# LED_SEMISEGMENT.net
KiCad netlist of a schematic drawn in Altium Designer
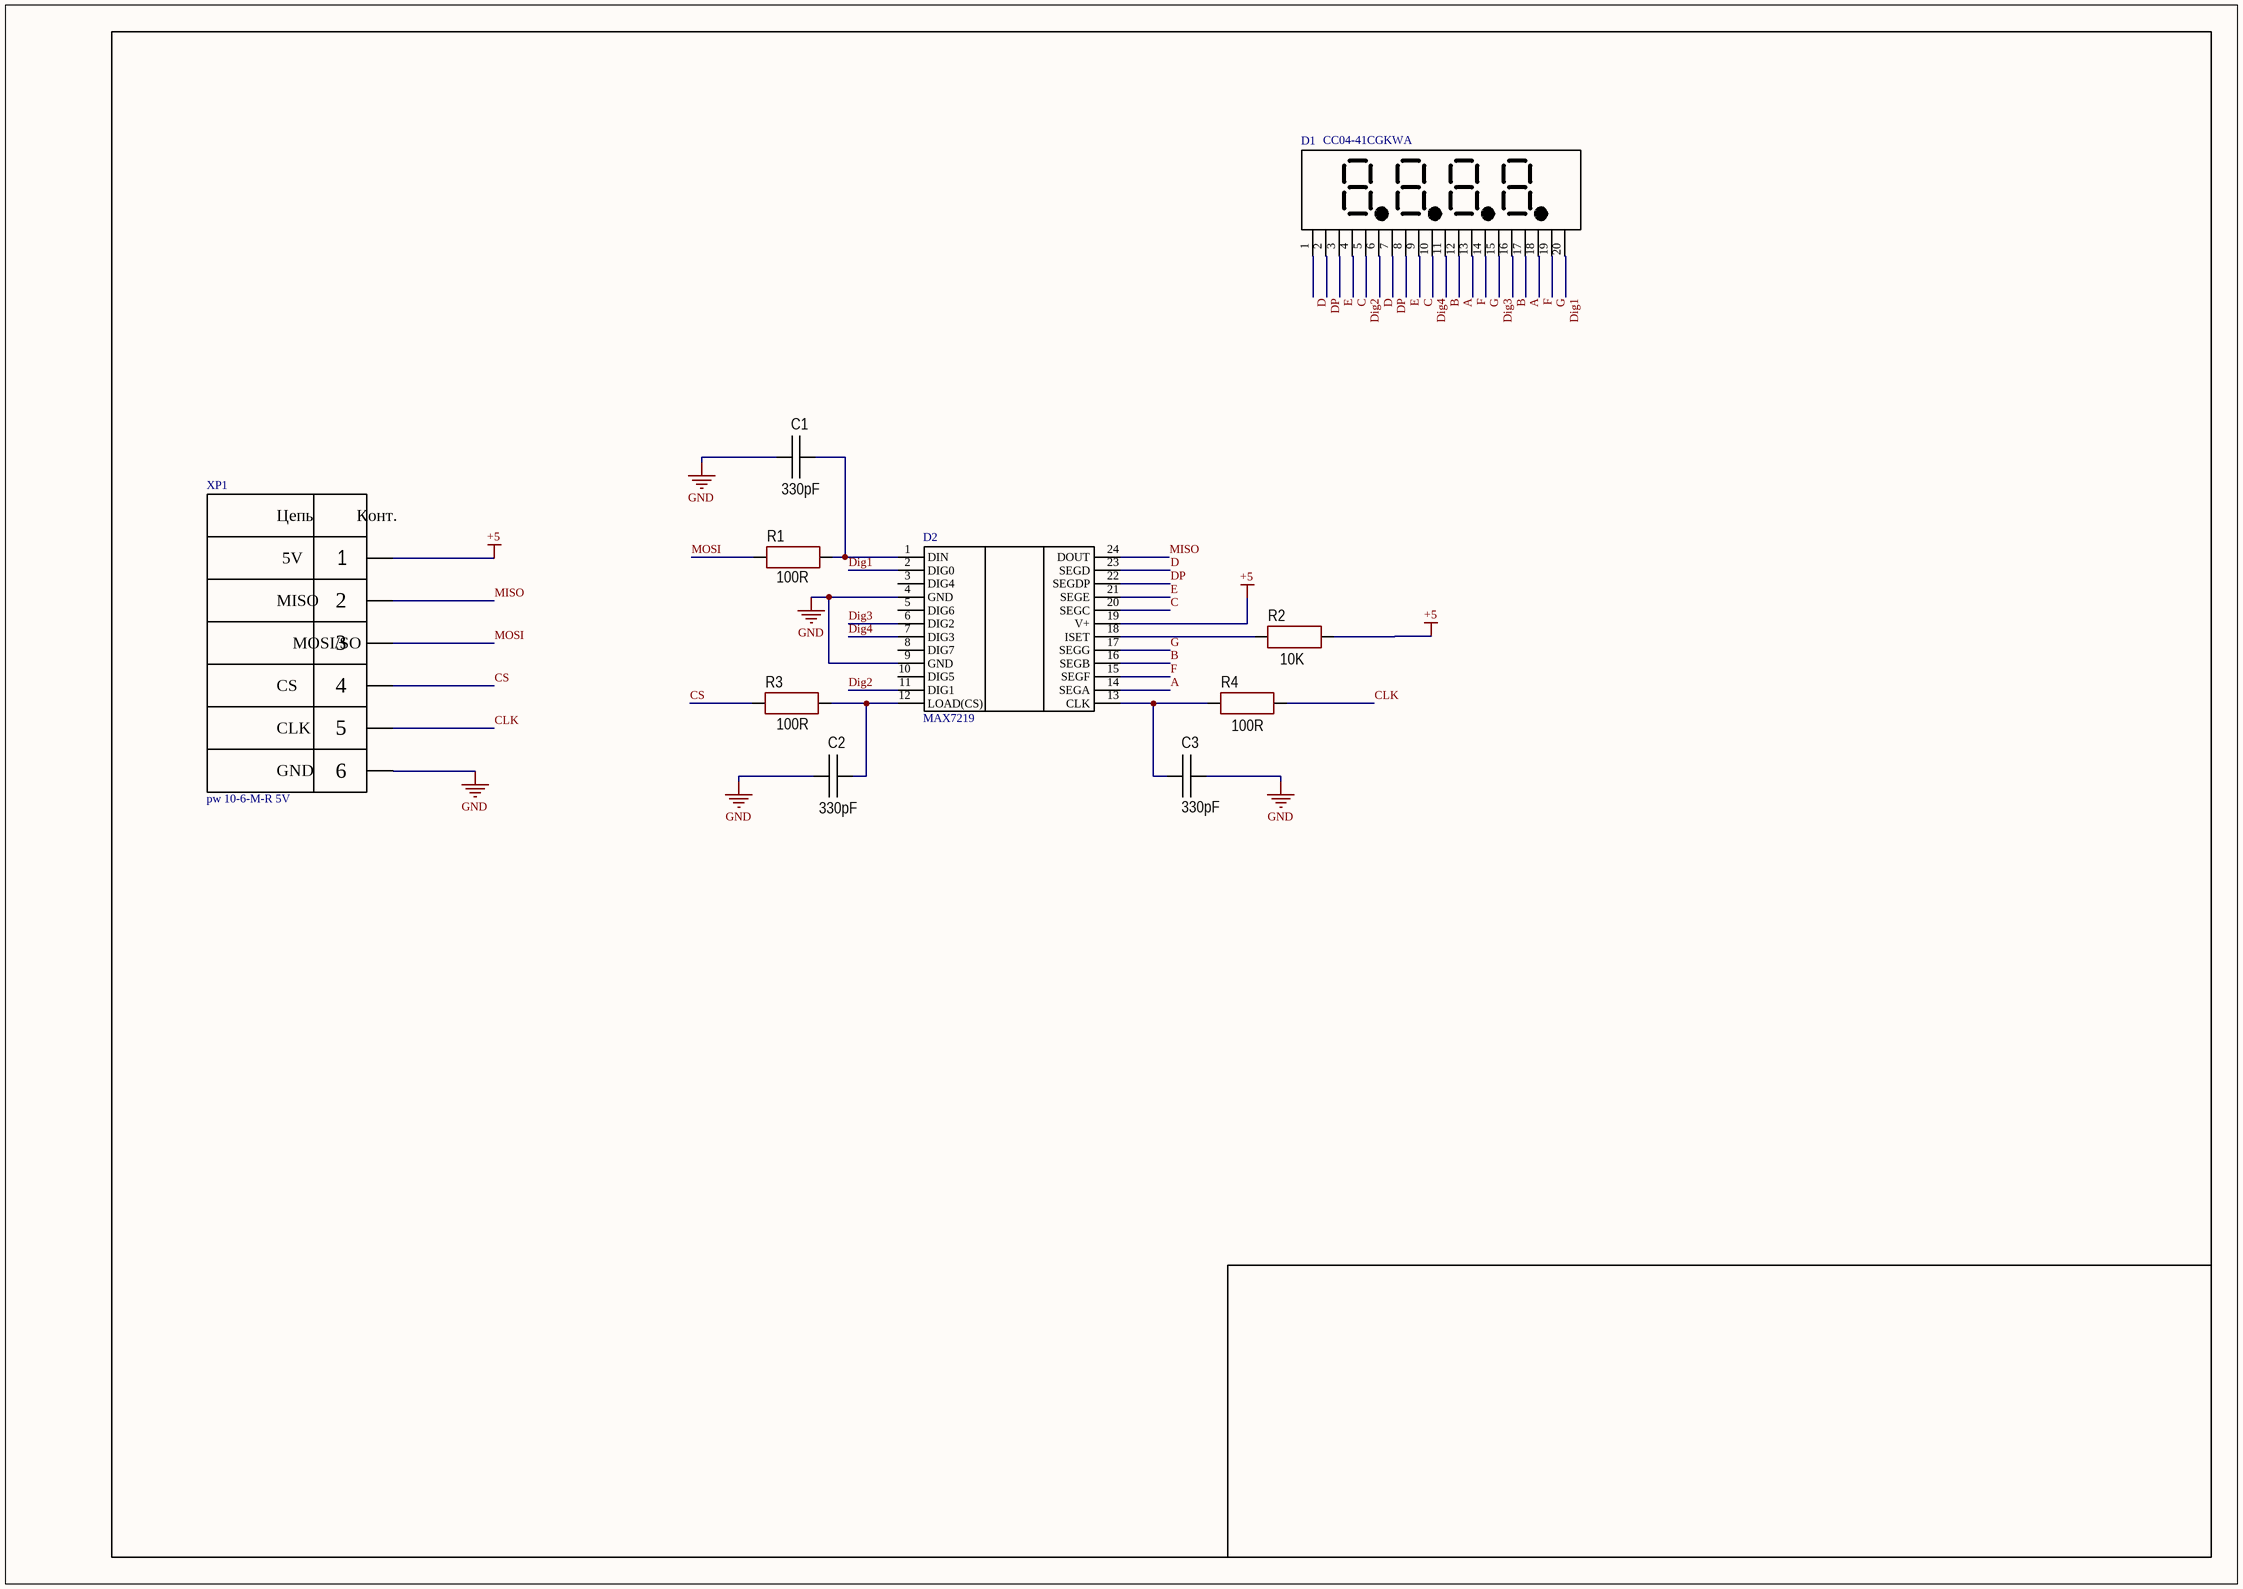
[diagram p0: LED_SEMISEGMENT.SchDoc]

(export (version "E")
  (design (tool "Eeschema 10.0.6"))
  (components
    (comp (ref "C1")
      (value "330pF")
      (footprint "CAP: 0805")
      (fields (field (name "VALUEMANUFACTURERPARTNUMBER") "Ceramic capacitor, 330pF, X7R, , , 0805, "))
      (libsource (lib "Capacitor") (part "Ceramic_0805"))
    )
    (comp (ref "C2")
      (value "330pF")
      (footprint "CAP: 0805")
      (fields (field (name "VALUEMANUFACTURERPARTNUMBER") "Ceramic capacitor, 330pF, X7R, , , 0805, "))
      (libsource (lib "Capacitor") (part "Ceramic_0805"))
    )
    (comp (ref "C3")
      (value "330pF")
      (footprint "CAP: 0805")
      (fields (field (name "VALUEMANUFACTURERPARTNUMBER") "Ceramic capacitor, 330pF, X7R, , , 0805, "))
      (libsource (lib "Capacitor") (part "Ceramic_0805"))
    )
    (comp (ref "D1")
      (value "CC04-41CGKWA")
      (footprint "7 segment x4")
      (libsource (lib "Integrated_Library") (part "LED_7x4"))
    )
    (comp (ref "D2")
      (value "MAX7219")
      (footprint "SOIC127P1030X265-24N")
      (libsource (lib "Integrated_Library") (part "MAX7219"))
    )
    (comp (ref "R1")
      (value "100R")
      (footprint "RES: 0805")
      (fields (field (name "VALUEMANUFACTURERPARTNUMBER") ", 100R, , 0805, , "))
      (libsource (lib "Resistor") (part "Resistor_0805"))
    )
    (comp (ref "R2")
      (value "10K")
      (footprint "RES: 0805")
      (fields (field (name "VALUEMANUFACTURERPARTNUMBER") ", 10K, , 0805, , "))
      (libsource (lib "Resistor") (part "Resistor_0805"))
    )
    (comp (ref "R3")
      (value "100R")
      (footprint "RES: 0805")
      (libsource (lib "Resistor") (part "Resistor_0805"))
    )
    (comp (ref "R4")
      (value "100R")
      (footprint "RES: 0805")
      (fields (field (name "VALUEMANUFACTURERPARTNUMBER") ", 100R, , 0805, , "))
      (libsource (lib "Resistor") (part "Resistor_0805"))
    )
    (comp (ref "XP1")
      (value "pw 10-6-M-R 5V")
      (footprint "PW 10-6-M")
      (libsource (lib "Integrated_Library") (part "pw 10-6-M-R 5V"))
    )
  )
  (nets
    (net (code "1") (name "+5") (class "Default")
      (node (ref "D2") (pin "19") (pinfunction "V+_19") (pintype "passive"))
      (node (ref "R2") (pin "2") (pinfunction "2_2") (pintype "passive"))
      (node (ref "XP1") (pin "1") (pinfunction "1_1") (pintype "passive"))
    )
    (net (code "3") (name "/A") (class "Default")
      (node (ref "D1") (pin "12") (pinfunction "12_12") (pintype "passive"))
      (node (ref "D1") (pin "17") (pinfunction "17_17") (pintype "passive"))
      (node (ref "D2") (pin "14") (pinfunction "SEGA_14") (pintype "passive"))
    )
    (net (code "4") (name "/B") (class "Default")
      (node (ref "D1") (pin "11") (pinfunction "11_11") (pintype "passive"))
      (node (ref "D1") (pin "16") (pinfunction "16_16") (pintype "passive"))
      (node (ref "D2") (pin "16") (pinfunction "SEGB_16") (pintype "passive"))
    )
    (net (code "5") (name "/C") (class "Default")
      (node (ref "D1") (pin "4") (pinfunction "4_4") (pintype "passive"))
      (node (ref "D1") (pin "9") (pinfunction "9_9") (pintype "passive"))
      (node (ref "D2") (pin "20") (pinfunction "SEGC_20") (pintype "passive"))
    )
    (net (code "6") (name "/CLK") (class "Default")
      (node (ref "R4") (pin "2") (pinfunction "2_2") (pintype "passive"))
      (node (ref "XP1") (pin "5") (pinfunction "5_5") (pintype "passive"))
    )
    (net (code "7") (name "/CS") (class "Default")
      (node (ref "R3") (pin "1") (pinfunction "1_1") (pintype "passive"))
      (node (ref "XP1") (pin "4") (pinfunction "4_4") (pintype "passive"))
    )
    (net (code "8") (name "/D") (class "Default")
      (node (ref "D1") (pin "1") (pinfunction "1_1") (pintype "passive"))
      (node (ref "D1") (pin "6") (pinfunction "6_6") (pintype "passive"))
      (node (ref "D2") (pin "23") (pinfunction "SEGD_23") (pintype "passive"))
    )
    (net (code "9") (name "/DP") (class "Default")
      (node (ref "D1") (pin "2") (pinfunction "2_2") (pintype "passive"))
      (node (ref "D1") (pin "7") (pinfunction "7_7") (pintype "passive"))
      (node (ref "D2") (pin "22") (pinfunction "SEGDP_22") (pintype "passive"))
    )
    (net (code "10") (name "/Dig1") (class "Default")
      (node (ref "D1") (pin "20") (pinfunction "20_20") (pintype "passive"))
      (node (ref "D2") (pin "2") (pinfunction "DIG0_2") (pintype "passive"))
    )
    (net (code "11") (name "/Dig2") (class "Default")
      (node (ref "D1") (pin "5") (pinfunction "5_5") (pintype "passive"))
      (node (ref "D2") (pin "11") (pinfunction "DIG1_11") (pintype "passive"))
    )
    (net (code "12") (name "/Dig3") (class "Default")
      (node (ref "D1") (pin "15") (pinfunction "15_15") (pintype "passive"))
      (node (ref "D2") (pin "6") (pinfunction "DIG2_6") (pintype "passive"))
    )
    (net (code "13") (name "/Dig4") (class "Default")
      (node (ref "D1") (pin "10") (pinfunction "10_10") (pintype "passive"))
      (node (ref "D2") (pin "7") (pinfunction "DIG3_7") (pintype "passive"))
    )
    (net (code "14") (name "/E") (class "Default")
      (node (ref "D1") (pin "3") (pinfunction "3_3") (pintype "passive"))
      (node (ref "D1") (pin "8") (pinfunction "8_8") (pintype "passive"))
      (node (ref "D2") (pin "21") (pinfunction "SEGE_21") (pintype "passive"))
    )
    (net (code "15") (name "/F") (class "Default")
      (node (ref "D1") (pin "13") (pinfunction "13_13") (pintype "passive"))
      (node (ref "D1") (pin "18") (pinfunction "18_18") (pintype "passive"))
      (node (ref "D2") (pin "15") (pinfunction "SEGF_15") (pintype "passive"))
    )
    (net (code "16") (name "/G") (class "Default")
      (node (ref "D1") (pin "14") (pinfunction "14_14") (pintype "passive"))
      (node (ref "D1") (pin "19") (pinfunction "19_19") (pintype "passive"))
      (node (ref "D2") (pin "17") (pinfunction "SEGG_17") (pintype "passive"))
    )
    (net (code "17") (name "/MISO") (class "Default")
      (node (ref "D2") (pin "24") (pinfunction "DOUT_24") (pintype "passive"))
      (node (ref "XP1") (pin "2") (pinfunction "2_2") (pintype "passive"))
    )
    (net (code "18") (name "/MOSI") (class "Default")
      (node (ref "R1") (pin "1") (pinfunction "1_1") (pintype "passive"))
      (node (ref "XP1") (pin "3") (pinfunction "3_3") (pintype "passive"))
    )
    (net (code "19") (name "GND") (class "Default")
      (node (ref "C1") (pin "2") (pinfunction "2_2") (pintype "power_in"))
      (node (ref "C2") (pin "2") (pinfunction "2_2") (pintype "power_in"))
      (node (ref "C3") (pin "2") (pinfunction "2_2") (pintype "power_in"))
      (node (ref "D2") (pin "4") (pinfunction "GND_4") (pintype "passive"))
      (node (ref "D2") (pin "9") (pinfunction "GND_9") (pintype "passive"))
      (node (ref "XP1") (pin "6") (pinfunction "6_6") (pintype "passive"))
    )
    (net (code "20") (name "Net-(D2-CLK)") (class "Default")
      (node (ref "C3") (pin "1") (pinfunction "1_1") (pintype "power_in"))
      (node (ref "D2") (pin "13") (pinfunction "CLK_13") (pintype "passive"))
      (node (ref "R4") (pin "1") (pinfunction "1_1") (pintype "passive"))
    )
    (net (code "21") (name "Net-(D2-DIN)") (class "Default")
      (node (ref "C1") (pin "1") (pinfunction "1_1") (pintype "power_in"))
      (node (ref "D2") (pin "1") (pinfunction "DIN_1") (pintype "passive"))
      (node (ref "R1") (pin "2") (pinfunction "2_2") (pintype "passive"))
    )
    (net (code "22") (name "Net-(D2-ISET)") (class "Default")
      (node (ref "D2") (pin "18") (pinfunction "ISET_18") (pintype "passive"))
      (node (ref "R2") (pin "1") (pinfunction "1_1") (pintype "passive"))
    )
    (net (code "23") (name "Net-(D2-LOAD(CS))") (class "Default")
      (node (ref "C2") (pin "1") (pinfunction "1_1") (pintype "power_in"))
      (node (ref "D2") (pin "12") (pinfunction "LOAD(CS)_12") (pintype "passive"))
      (node (ref "R3") (pin "2") (pinfunction "2_2") (pintype "passive"))
    )
    (net (code "24") (name "unconnected-(D2-DIG4-Pad3)") (class "Default")
      (node (ref "D2") (pin "3") (pinfunction "DIG4_3") (pintype "passive"))
    )
    (net (code "25") (name "unconnected-(D2-DIG5-Pad10)") (class "Default")
      (node (ref "D2") (pin "10") (pinfunction "DIG5_10") (pintype "passive"))
    )
    (net (code "26") (name "unconnected-(D2-DIG6-Pad5)") (class "Default")
      (node (ref "D2") (pin "5") (pinfunction "DIG6_5") (pintype "passive"))
    )
    (net (code "27") (name "unconnected-(D2-DIG7-Pad8)") (class "Default")
      (node (ref "D2") (pin "8") (pinfunction "DIG7_8") (pintype "passive"))
    )
  )
)
